# SparkFun_IMU_Breakout_ICM-20948_v1.net
KiCad netlist of a schematic drawn in EAGLE
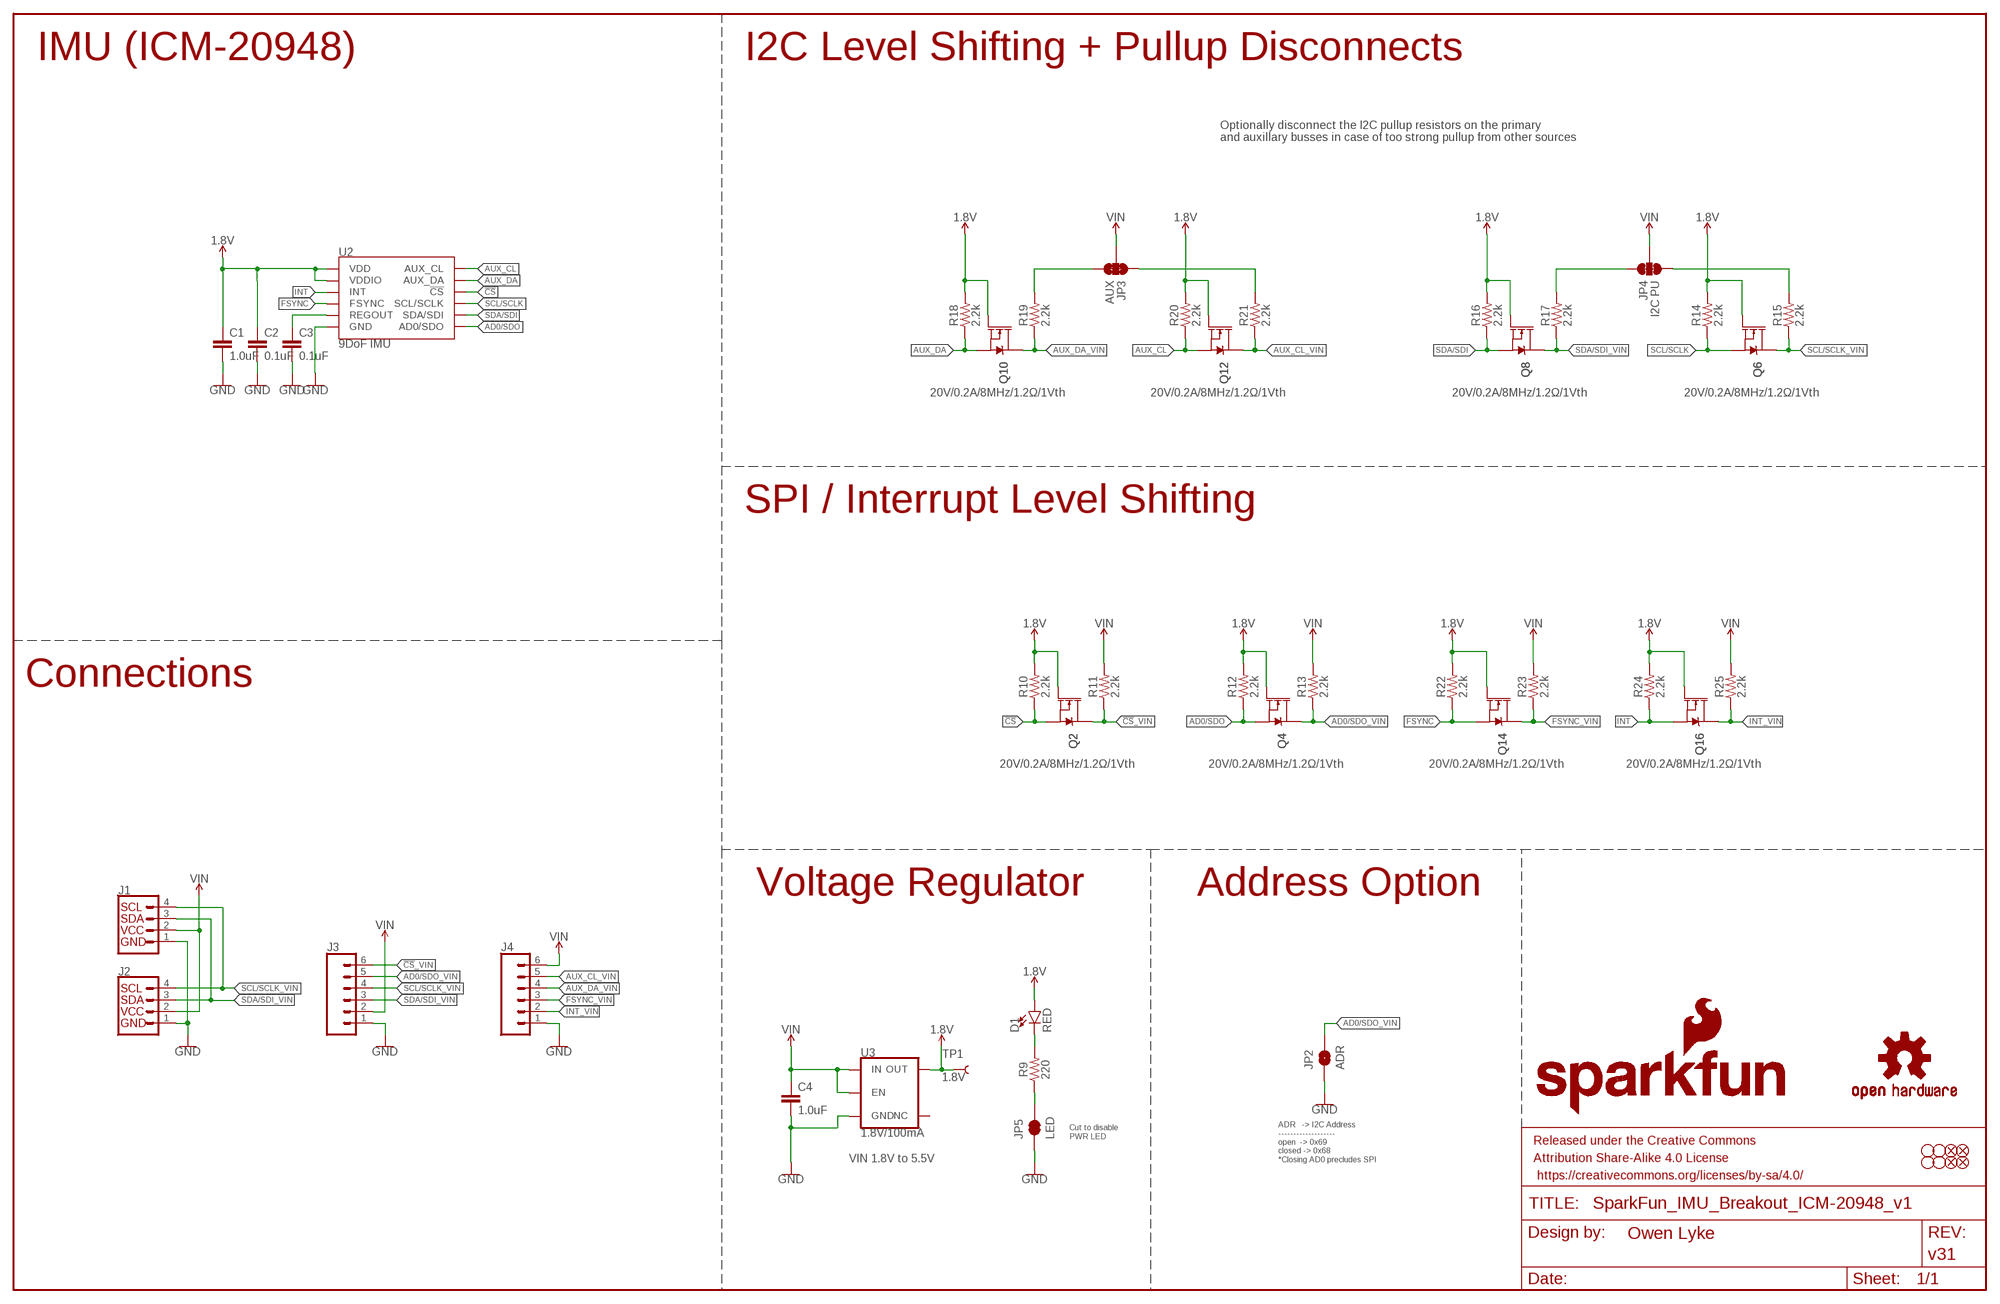
[diagram p0: schematic, sheet 1]

(export (version "E")
  (design (tool "Eeschema 10.0.6"))
  (components
    (comp (ref "C1")
      (value "1.0uF")
      (footprint "eagle-import:0603")
      (libsource (lib "eagle-import") (part "1.0UF-0603-16V-10%-X7R"))
    )
    (comp (ref "C2")
      (value "0.1uF")
      (footprint "eagle-import:0603")
      (libsource (lib "eagle-import") (part "0.1UF-0603-25V-5%"))
    )
    (comp (ref "C3")
      (value "0.1uF")
      (footprint "eagle-import:0603")
      (libsource (lib "eagle-import") (part "0.1UF-0603-25V-5%"))
    )
    (comp (ref "C4")
      (value "1.0uF")
      (footprint "eagle-import:0603")
      (libsource (lib "eagle-import") (part "1.0UF-0603-16V-10%-X7R"))
    )
    (comp (ref "D1")
      (value "RED")
      (footprint "eagle-import:LED-0603")
      (libsource (lib "eagle-import") (part "LED-RED0603"))
    )
    (comp (ref "FD1")
      (value "FIDUCIAL1X2")
      (footprint "eagle-import:FIDUCIAL-1X2")
      (libsource (lib "eagle-import") (part "FIDUCIAL1X2"))
    )
    (comp (ref "FD2")
      (value "FIDUCIAL1X2")
      (footprint "eagle-import:FIDUCIAL-1X2")
      (libsource (lib "eagle-import") (part "FIDUCIAL1X2"))
    )
    (comp (ref "FD3")
      (value "FIDUCIAL1X2")
      (footprint "eagle-import:FIDUCIAL-1X2")
      (libsource (lib "eagle-import") (part "FIDUCIAL1X2"))
    )
    (comp (ref "FD4")
      (value "FIDUCIAL1X2")
      (footprint "eagle-import:FIDUCIAL-1X2")
      (libsource (lib "eagle-import") (part "FIDUCIAL1X2"))
    )
    (comp (ref "FRAME2")
      (value "FRAME-LEDGER")
      (footprint "eagle-import:CREATIVE_COMMONS")
      (fields (field (name "DESIGNER") "Owen Lyke") (field (name "REV") "v31"))
      (libsource (lib "eagle-import") (part "FRAME-LEDGER"))
    )
    (comp (ref "H1")
      (value "STAND-OFF")
      (footprint "eagle-import:STAND-OFF")
      (libsource (lib "eagle-import") (part "STAND-OFF"))
    )
    (comp (ref "H2")
      (value "STAND-OFF")
      (footprint "eagle-import:STAND-OFF")
      (libsource (lib "eagle-import") (part "STAND-OFF"))
    )
    (comp (ref "H3")
      (value "STAND-OFF")
      (footprint "eagle-import:STAND-OFF")
      (libsource (lib "eagle-import") (part "STAND-OFF"))
    )
    (comp (ref "H4")
      (value "STAND-OFF")
      (footprint "eagle-import:STAND-OFF")
      (libsource (lib "eagle-import") (part "STAND-OFF"))
    )
    (comp (ref "J1")
      (value "QWIIC_CONNECTORJS-1MM")
      (footprint "eagle-import:JST04_1MM_RA")
      (libsource (lib "eagle-import") (part "QWIIC_CONNECTORJS-1MM"))
    )
    (comp (ref "J2")
      (value "QWIIC_CONNECTORJS-1MM")
      (footprint "eagle-import:JST04_1MM_RA")
      (libsource (lib "eagle-import") (part "QWIIC_CONNECTORJS-1MM"))
    )
    (comp (ref "J3")
      (value "CONN_06NO_SILK_NO_POP")
      (footprint "eagle-import:1X06_NO_SILK")
      (libsource (lib "eagle-import") (part "CONN_06NO_SILK_NO_POP"))
    )
    (comp (ref "J4")
      (value "CONN_06NO_SILK_NO_POP")
      (footprint "eagle-import:1X06_NO_SILK")
      (libsource (lib "eagle-import") (part "CONN_06NO_SILK_NO_POP"))
    )
    (comp (ref "JP2")
      (value "ADR")
      (footprint "eagle-import:SMT-JUMPER_2_NO_SILK")
      (libsource (lib "eagle-import") (part "JUMPER-SMT_2_NO_SILK"))
    )
    (comp (ref "JP3")
      (value "AUX")
      (footprint "eagle-import:SMT-JUMPER_3_2-NC_TRACE_SILK")
      (libsource (lib "eagle-import") (part "JUMPER-SMT_3_2-NC_TRACE_SILK"))
    )
    (comp (ref "JP4")
      (value "I2C PU")
      (footprint "eagle-import:SMT-JUMPER_3_2-NC_TRACE_SILK")
      (libsource (lib "eagle-import") (part "JUMPER-SMT_3_2-NC_TRACE_SILK"))
    )
    (comp (ref "JP5")
      (value "LED")
      (footprint "eagle-import:SMT-JUMPER_2_NC_TRACE_SILK")
      (libsource (lib "eagle-import") (part "JUMPER-SMT_2_NC_TRACE_SILK"))
    )
    (comp (ref "LOGO1")
      (value "SFE_LOGO_NAME_FLAME.1_INCH")
      (footprint "eagle-import:SFE_LOGO_NAME_FLAME_.1")
      (libsource (lib "eagle-import") (part "SFE_LOGO_NAME_FLAME.1_INCH"))
    )
    (comp (ref "LOGO2")
      (value "OSHW-LOGOMINI")
      (footprint "eagle-import:OSHW-LOGO-MINI")
      (libsource (lib "eagle-import") (part "OSHW-LOGOMINI"))
    )
    (comp (ref "Q2")
      (value "20V/0.2A/8MHz/1.2Ω/1Vth")
      (footprint "eagle-import:SOT-416FL")
      (libsource (lib "eagle-import") (part "MOSFET-NCH-RE1C002UN"))
    )
    (comp (ref "Q4")
      (value "20V/0.2A/8MHz/1.2Ω/1Vth")
      (footprint "eagle-import:SOT-416FL")
      (libsource (lib "eagle-import") (part "MOSFET-NCH-RE1C002UN"))
    )
    (comp (ref "Q6")
      (value "20V/0.2A/8MHz/1.2Ω/1Vth")
      (footprint "eagle-import:SOT-416FL")
      (libsource (lib "eagle-import") (part "MOSFET-NCH-RE1C002UN"))
    )
    (comp (ref "Q8")
      (value "20V/0.2A/8MHz/1.2Ω/1Vth")
      (footprint "eagle-import:SOT-416FL")
      (libsource (lib "eagle-import") (part "MOSFET-NCH-RE1C002UN"))
    )
    (comp (ref "Q10")
      (value "20V/0.2A/8MHz/1.2Ω/1Vth")
      (footprint "eagle-import:SOT-416FL")
      (libsource (lib "eagle-import") (part "MOSFET-NCH-RE1C002UN"))
    )
    (comp (ref "Q12")
      (value "20V/0.2A/8MHz/1.2Ω/1Vth")
      (footprint "eagle-import:SOT-416FL")
      (libsource (lib "eagle-import") (part "MOSFET-NCH-RE1C002UN"))
    )
    (comp (ref "Q14")
      (value "20V/0.2A/8MHz/1.2Ω/1Vth")
      (footprint "eagle-import:SOT-416FL")
      (libsource (lib "eagle-import") (part "MOSFET-NCH-RE1C002UN"))
    )
    (comp (ref "Q16")
      (value "20V/0.2A/8MHz/1.2Ω/1Vth")
      (footprint "eagle-import:SOT-416FL")
      (libsource (lib "eagle-import") (part "MOSFET-NCH-RE1C002UN"))
    )
    (comp (ref "R9")
      (value "220")
      (footprint "eagle-import:0603")
      (libsource (lib "eagle-import") (part "220OHM-0603-1/10W-1%"))
    )
    (comp (ref "R10")
      (value "2.2k")
      (footprint "eagle-import:0402-TIGHT")
      (libsource (lib "eagle-import") (part "2.2KOHM-0402T-1/16W-1%"))
    )
    (comp (ref "R11")
      (value "2.2k")
      (footprint "eagle-import:0402-TIGHT")
      (libsource (lib "eagle-import") (part "2.2KOHM-0402T-1/16W-1%"))
    )
    (comp (ref "R12")
      (value "2.2k")
      (footprint "eagle-import:0402-TIGHT")
      (libsource (lib "eagle-import") (part "2.2KOHM-0402T-1/16W-1%"))
    )
    (comp (ref "R13")
      (value "2.2k")
      (footprint "eagle-import:0402-TIGHT")
      (libsource (lib "eagle-import") (part "2.2KOHM-0402T-1/16W-1%"))
    )
    (comp (ref "R14")
      (value "2.2k")
      (footprint "eagle-import:0402-TIGHT")
      (libsource (lib "eagle-import") (part "2.2KOHM-0402T-1/16W-1%"))
    )
    (comp (ref "R15")
      (value "2.2k")
      (footprint "eagle-import:0402-TIGHT")
      (libsource (lib "eagle-import") (part "2.2KOHM-0402T-1/16W-1%"))
    )
    (comp (ref "R16")
      (value "2.2k")
      (footprint "eagle-import:0402-TIGHT")
      (libsource (lib "eagle-import") (part "2.2KOHM-0402T-1/16W-1%"))
    )
    (comp (ref "R17")
      (value "2.2k")
      (footprint "eagle-import:0402-TIGHT")
      (libsource (lib "eagle-import") (part "2.2KOHM-0402T-1/16W-1%"))
    )
    (comp (ref "R18")
      (value "2.2k")
      (footprint "eagle-import:0402-TIGHT")
      (libsource (lib "eagle-import") (part "2.2KOHM-0402T-1/16W-1%"))
    )
    (comp (ref "R19")
      (value "2.2k")
      (footprint "eagle-import:0402-TIGHT")
      (libsource (lib "eagle-import") (part "2.2KOHM-0402T-1/16W-1%"))
    )
    (comp (ref "R20")
      (value "2.2k")
      (footprint "eagle-import:0402-TIGHT")
      (libsource (lib "eagle-import") (part "2.2KOHM-0402T-1/16W-1%"))
    )
    (comp (ref "R21")
      (value "2.2k")
      (footprint "eagle-import:0402-TIGHT")
      (libsource (lib "eagle-import") (part "2.2KOHM-0402T-1/16W-1%"))
    )
    (comp (ref "R22")
      (value "2.2k")
      (footprint "eagle-import:0402-TIGHT")
      (libsource (lib "eagle-import") (part "2.2KOHM-0402T-1/16W-1%"))
    )
    (comp (ref "R23")
      (value "2.2k")
      (footprint "eagle-import:0402-TIGHT")
      (libsource (lib "eagle-import") (part "2.2KOHM-0402T-1/16W-1%"))
    )
    (comp (ref "R24")
      (value "2.2k")
      (footprint "eagle-import:0402-TIGHT")
      (libsource (lib "eagle-import") (part "2.2KOHM-0402T-1/16W-1%"))
    )
    (comp (ref "R25")
      (value "2.2k")
      (footprint "eagle-import:0402-TIGHT")
      (libsource (lib "eagle-import") (part "2.2KOHM-0402T-1/16W-1%"))
    )
    (comp (ref "TP1")
      (value "1.8V")
      (footprint "eagle-import:PAD.03X.03")
      (libsource (lib "eagle-import") (part "TEST-POINT3"))
    )
    (comp (ref "U2")
      (value "9DoF IMU")
      (footprint "eagle-import:QFN24-3X3")
      (libsource (lib "eagle-import") (part "ICM-20948"))
    )
    (comp (ref "U3")
      (value "1.8V/100mA")
      (footprint "eagle-import:SC70")
      (libsource (lib "eagle-import") (part "V_REG_SP6214-1.8V"))
    )
  )
  (nets
    (net (code "1") (name "/~{CS}") (class "Default")
      (node (ref "Q2") (pin "2") (pinfunction "S_2") (pintype "bidirectional"))
      (node (ref "R10") (pin "1") (pinfunction "1_1") (pintype "passive"))
      (node (ref "U2") (pin "22") (pinfunction "~{CS}_22") (pintype "bidirectional"))
    )
    (net (code "2") (name "/~{CS}_VIN") (class "Default")
      (node (ref "J3") (pin "6") (pinfunction "6_6") (pintype "passive"))
      (node (ref "Q2") (pin "3") (pinfunction "D_3") (pintype "bidirectional"))
      (node (ref "R11") (pin "1") (pinfunction "1_1") (pintype "passive"))
    )
    (net (code "3") (name "1.8V") (class "Default")
      (node (ref "C1") (pin "1") (pinfunction "1_1") (pintype "passive"))
      (node (ref "C2") (pin "1") (pinfunction "1_1") (pintype "passive"))
      (node (ref "D1") (pin "A") (pinfunction "A_A") (pintype "passive"))
      (node (ref "Q10") (pin "1") (pinfunction "G_1") (pintype "bidirectional"))
      (node (ref "Q12") (pin "1") (pinfunction "G_1") (pintype "bidirectional"))
      (node (ref "Q14") (pin "1") (pinfunction "G_1") (pintype "bidirectional"))
      (node (ref "Q16") (pin "1") (pinfunction "G_1") (pintype "bidirectional"))
      (node (ref "Q2") (pin "1") (pinfunction "G_1") (pintype "bidirectional"))
      (node (ref "Q4") (pin "1") (pinfunction "G_1") (pintype "bidirectional"))
      (node (ref "Q6") (pin "1") (pinfunction "G_1") (pintype "bidirectional"))
      (node (ref "Q8") (pin "1") (pinfunction "G_1") (pintype "bidirectional"))
      (node (ref "R10") (pin "2") (pinfunction "2_2") (pintype "passive"))
      (node (ref "R12") (pin "2") (pinfunction "2_2") (pintype "passive"))
      (node (ref "R14") (pin "2") (pinfunction "2_2") (pintype "passive"))
      (node (ref "R16") (pin "2") (pinfunction "2_2") (pintype "passive"))
      (node (ref "R18") (pin "2") (pinfunction "2_2") (pintype "passive"))
      (node (ref "R20") (pin "2") (pinfunction "2_2") (pintype "passive"))
      (node (ref "R22") (pin "2") (pinfunction "2_2") (pintype "passive"))
      (node (ref "R24") (pin "2") (pinfunction "2_2") (pintype "passive"))
      (node (ref "TP1") (pin "P$1") (pinfunction "1_P$1") (pintype "bidirectional"))
      (node (ref "U2") (pin "13") (pinfunction "VDD_13") (pintype "bidirectional"))
      (node (ref "U2") (pin "8") (pinfunction "VDDIO_8") (pintype "bidirectional"))
      (node (ref "U3") (pin "5") (pinfunction "OUT_5") (pintype "passive"))
    )
    (net (code "4") (name "AD0{slash}SDO") (class "Default")
      (node (ref "Q4") (pin "2") (pinfunction "S_2") (pintype "bidirectional"))
      (node (ref "R12") (pin "1") (pinfunction "1_1") (pintype "passive"))
      (node (ref "U2") (pin "9") (pinfunction "AD0/SDO_9") (pintype "bidirectional"))
    )
    (net (code "5") (name "AD0{slash}SDO_VIN") (class "Default")
      (node (ref "J3") (pin "5") (pinfunction "5_5") (pintype "passive"))
      (node (ref "JP2") (pin "2") (pinfunction "2_2") (pintype "passive"))
      (node (ref "Q4") (pin "3") (pinfunction "D_3") (pintype "bidirectional"))
      (node (ref "R13") (pin "1") (pinfunction "1_1") (pintype "passive"))
    )
    (net (code "6") (name "AUX_CL") (class "Default")
      (node (ref "Q12") (pin "2") (pinfunction "S_2") (pintype "bidirectional"))
      (node (ref "R20") (pin "1") (pinfunction "1_1") (pintype "passive"))
      (node (ref "U2") (pin "7") (pinfunction "AUX_CL_7") (pintype "bidirectional"))
    )
    (net (code "7") (name "AUX_CL_VIN") (class "Default")
      (node (ref "J4") (pin "5") (pinfunction "5_5") (pintype "passive"))
      (node (ref "Q12") (pin "3") (pinfunction "D_3") (pintype "bidirectional"))
      (node (ref "R21") (pin "1") (pinfunction "1_1") (pintype "passive"))
    )
    (net (code "8") (name "AUX_DA") (class "Default")
      (node (ref "Q10") (pin "2") (pinfunction "S_2") (pintype "bidirectional"))
      (node (ref "R18") (pin "1") (pinfunction "1_1") (pintype "passive"))
      (node (ref "U2") (pin "21") (pinfunction "AUX_DA_21") (pintype "bidirectional"))
    )
    (net (code "9") (name "AUX_DA_VIN") (class "Default")
      (node (ref "J4") (pin "4") (pinfunction "4_4") (pintype "passive"))
      (node (ref "Q10") (pin "3") (pinfunction "D_3") (pintype "bidirectional"))
      (node (ref "R19") (pin "1") (pinfunction "1_1") (pintype "passive"))
    )
    (net (code "10") (name "FSYNC") (class "Default")
      (node (ref "Q14") (pin "2") (pinfunction "S_2") (pintype "bidirectional"))
      (node (ref "R22") (pin "1") (pinfunction "1_1") (pintype "passive"))
      (node (ref "U2") (pin "11") (pinfunction "FSYNC_11") (pintype "bidirectional"))
    )
    (net (code "11") (name "FSYNC_VIN") (class "Default")
      (node (ref "J4") (pin "3") (pinfunction "3_3") (pintype "passive"))
      (node (ref "Q14") (pin "3") (pinfunction "D_3") (pintype "bidirectional"))
      (node (ref "R23") (pin "1") (pinfunction "1_1") (pintype "passive"))
    )
    (net (code "12") (name "GND") (class "Default")
      (node (ref "C1") (pin "2") (pinfunction "2_2") (pintype "passive"))
      (node (ref "C2") (pin "2") (pinfunction "2_2") (pintype "passive"))
      (node (ref "C3") (pin "2") (pinfunction "2_2") (pintype "passive"))
      (node (ref "C4") (pin "2") (pinfunction "2_2") (pintype "passive"))
      (node (ref "J1") (pin "1") (pinfunction "1_1") (pintype "power_in"))
      (node (ref "J2") (pin "1") (pinfunction "1_1") (pintype "power_in"))
      (node (ref "J3") (pin "1") (pinfunction "1_1") (pintype "passive"))
      (node (ref "J4") (pin "1") (pinfunction "1_1") (pintype "passive"))
      (node (ref "JP2") (pin "1") (pinfunction "1_1") (pintype "passive"))
      (node (ref "JP5") (pin "1") (pinfunction "1_1") (pintype "passive"))
      (node (ref "U2") (pin "18") (pinfunction "GND_18") (pintype "bidirectional"))
      (node (ref "U2") (pin "20") (pinfunction "GND_20") (pintype "bidirectional"))
      (node (ref "U3") (pin "2") (pinfunction "GND_2") (pintype "input"))
    )
    (net (code "13") (name "INT") (class "Default")
      (node (ref "Q16") (pin "2") (pinfunction "S_2") (pintype "bidirectional"))
      (node (ref "R24") (pin "1") (pinfunction "1_1") (pintype "passive"))
      (node (ref "U2") (pin "12") (pinfunction "INT_12") (pintype "bidirectional"))
    )
    (net (code "14") (name "INT_VIN") (class "Default")
      (node (ref "J4") (pin "2") (pinfunction "2_2") (pintype "passive"))
      (node (ref "Q16") (pin "3") (pinfunction "D_3") (pintype "bidirectional"))
      (node (ref "R25") (pin "1") (pinfunction "1_1") (pintype "passive"))
    )
    (net (code "15") (name "Net-(D1-PadC)") (class "Default")
      (node (ref "D1") (pin "C") (pinfunction "C_C") (pintype "passive"))
      (node (ref "R9") (pin "2") (pinfunction "2_2") (pintype "passive"))
    )
    (net (code "16") (name "Net-(JP3-Pad1)") (class "Default")
      (node (ref "JP3") (pin "1") (pinfunction "1_1") (pintype "passive"))
      (node (ref "R21") (pin "2") (pinfunction "2_2") (pintype "passive"))
    )
    (net (code "17") (name "Net-(JP3-Pad3)") (class "Default")
      (node (ref "JP3") (pin "3") (pinfunction "3_3") (pintype "passive"))
      (node (ref "R19") (pin "2") (pinfunction "2_2") (pintype "passive"))
    )
    (net (code "18") (name "Net-(JP4-Pad1)") (class "Default")
      (node (ref "JP4") (pin "1") (pinfunction "1_1") (pintype "passive"))
      (node (ref "R17") (pin "2") (pinfunction "2_2") (pintype "passive"))
    )
    (net (code "19") (name "Net-(JP4-Pad3)") (class "Default")
      (node (ref "JP4") (pin "3") (pinfunction "3_3") (pintype "passive"))
      (node (ref "R15") (pin "2") (pinfunction "2_2") (pintype "passive"))
    )
    (net (code "20") (name "Net-(JP5-Pad2)") (class "Default")
      (node (ref "JP5") (pin "2") (pinfunction "2_2") (pintype "passive"))
      (node (ref "R9") (pin "1") (pinfunction "1_1") (pintype "passive"))
    )
    (net (code "21") (name "Net-(U2-REGOUT)") (class "Default")
      (node (ref "C3") (pin "1") (pinfunction "1_1") (pintype "passive"))
      (node (ref "U2") (pin "10") (pinfunction "REGOUT_10") (pintype "bidirectional"))
    )
    (net (code "22") (name "SCL{slash}SCLK") (class "Default")
      (node (ref "Q6") (pin "2") (pinfunction "S_2") (pintype "bidirectional"))
      (node (ref "R14") (pin "1") (pinfunction "1_1") (pintype "passive"))
      (node (ref "U2") (pin "23") (pinfunction "SCL/SCLK_23") (pintype "bidirectional"))
    )
    (net (code "23") (name "SCL{slash}SCLK_VIN") (class "Default")
      (node (ref "J1") (pin "4") (pinfunction "4_4") (pintype "passive"))
      (node (ref "J2") (pin "4") (pinfunction "4_4") (pintype "passive"))
      (node (ref "J3") (pin "4") (pinfunction "4_4") (pintype "passive"))
      (node (ref "Q6") (pin "3") (pinfunction "D_3") (pintype "bidirectional"))
      (node (ref "R15") (pin "1") (pinfunction "1_1") (pintype "passive"))
    )
    (net (code "24") (name "SDA{slash}SDI") (class "Default")
      (node (ref "Q8") (pin "2") (pinfunction "S_2") (pintype "bidirectional"))
      (node (ref "R16") (pin "1") (pinfunction "1_1") (pintype "passive"))
      (node (ref "U2") (pin "24") (pinfunction "SDA/SDI_24") (pintype "bidirectional"))
    )
    (net (code "25") (name "SDA{slash}SDI_VIN") (class "Default")
      (node (ref "J1") (pin "3") (pinfunction "3_3") (pintype "passive"))
      (node (ref "J2") (pin "3") (pinfunction "3_3") (pintype "passive"))
      (node (ref "J3") (pin "3") (pinfunction "3_3") (pintype "passive"))
      (node (ref "Q8") (pin "3") (pinfunction "D_3") (pintype "bidirectional"))
      (node (ref "R17") (pin "1") (pinfunction "1_1") (pintype "passive"))
    )
    (net (code "26") (name "VIN") (class "Default")
      (node (ref "C4") (pin "1") (pinfunction "1_1") (pintype "passive"))
      (node (ref "J1") (pin "2") (pinfunction "2_2") (pintype "power_in"))
      (node (ref "J2") (pin "2") (pinfunction "2_2") (pintype "power_in"))
      (node (ref "J3") (pin "2") (pinfunction "2_2") (pintype "passive"))
      (node (ref "J4") (pin "6") (pinfunction "6_6") (pintype "passive"))
      (node (ref "JP3") (pin "2") (pinfunction "2_2") (pintype "passive"))
      (node (ref "JP4") (pin "2") (pinfunction "2_2") (pintype "passive"))
      (node (ref "R11") (pin "2") (pinfunction "2_2") (pintype "passive"))
      (node (ref "R13") (pin "2") (pinfunction "2_2") (pintype "passive"))
      (node (ref "R23") (pin "2") (pinfunction "2_2") (pintype "passive"))
      (node (ref "R25") (pin "2") (pinfunction "2_2") (pintype "passive"))
      (node (ref "U3") (pin "1") (pinfunction "IN_1") (pintype "input"))
      (node (ref "U3") (pin "3") (pinfunction "EN_3") (pintype "input"))
    )
    (net (code "27") (name "unconnected-(U3-NC-Pad4)") (class "Default")
      (node (ref "U3") (pin "4") (pinfunction "NC_4") (pintype "no_connect"))
    )
  )
)
